# MCU-BLE.net
KiCad netlist of a schematic drawn in Altium Designer
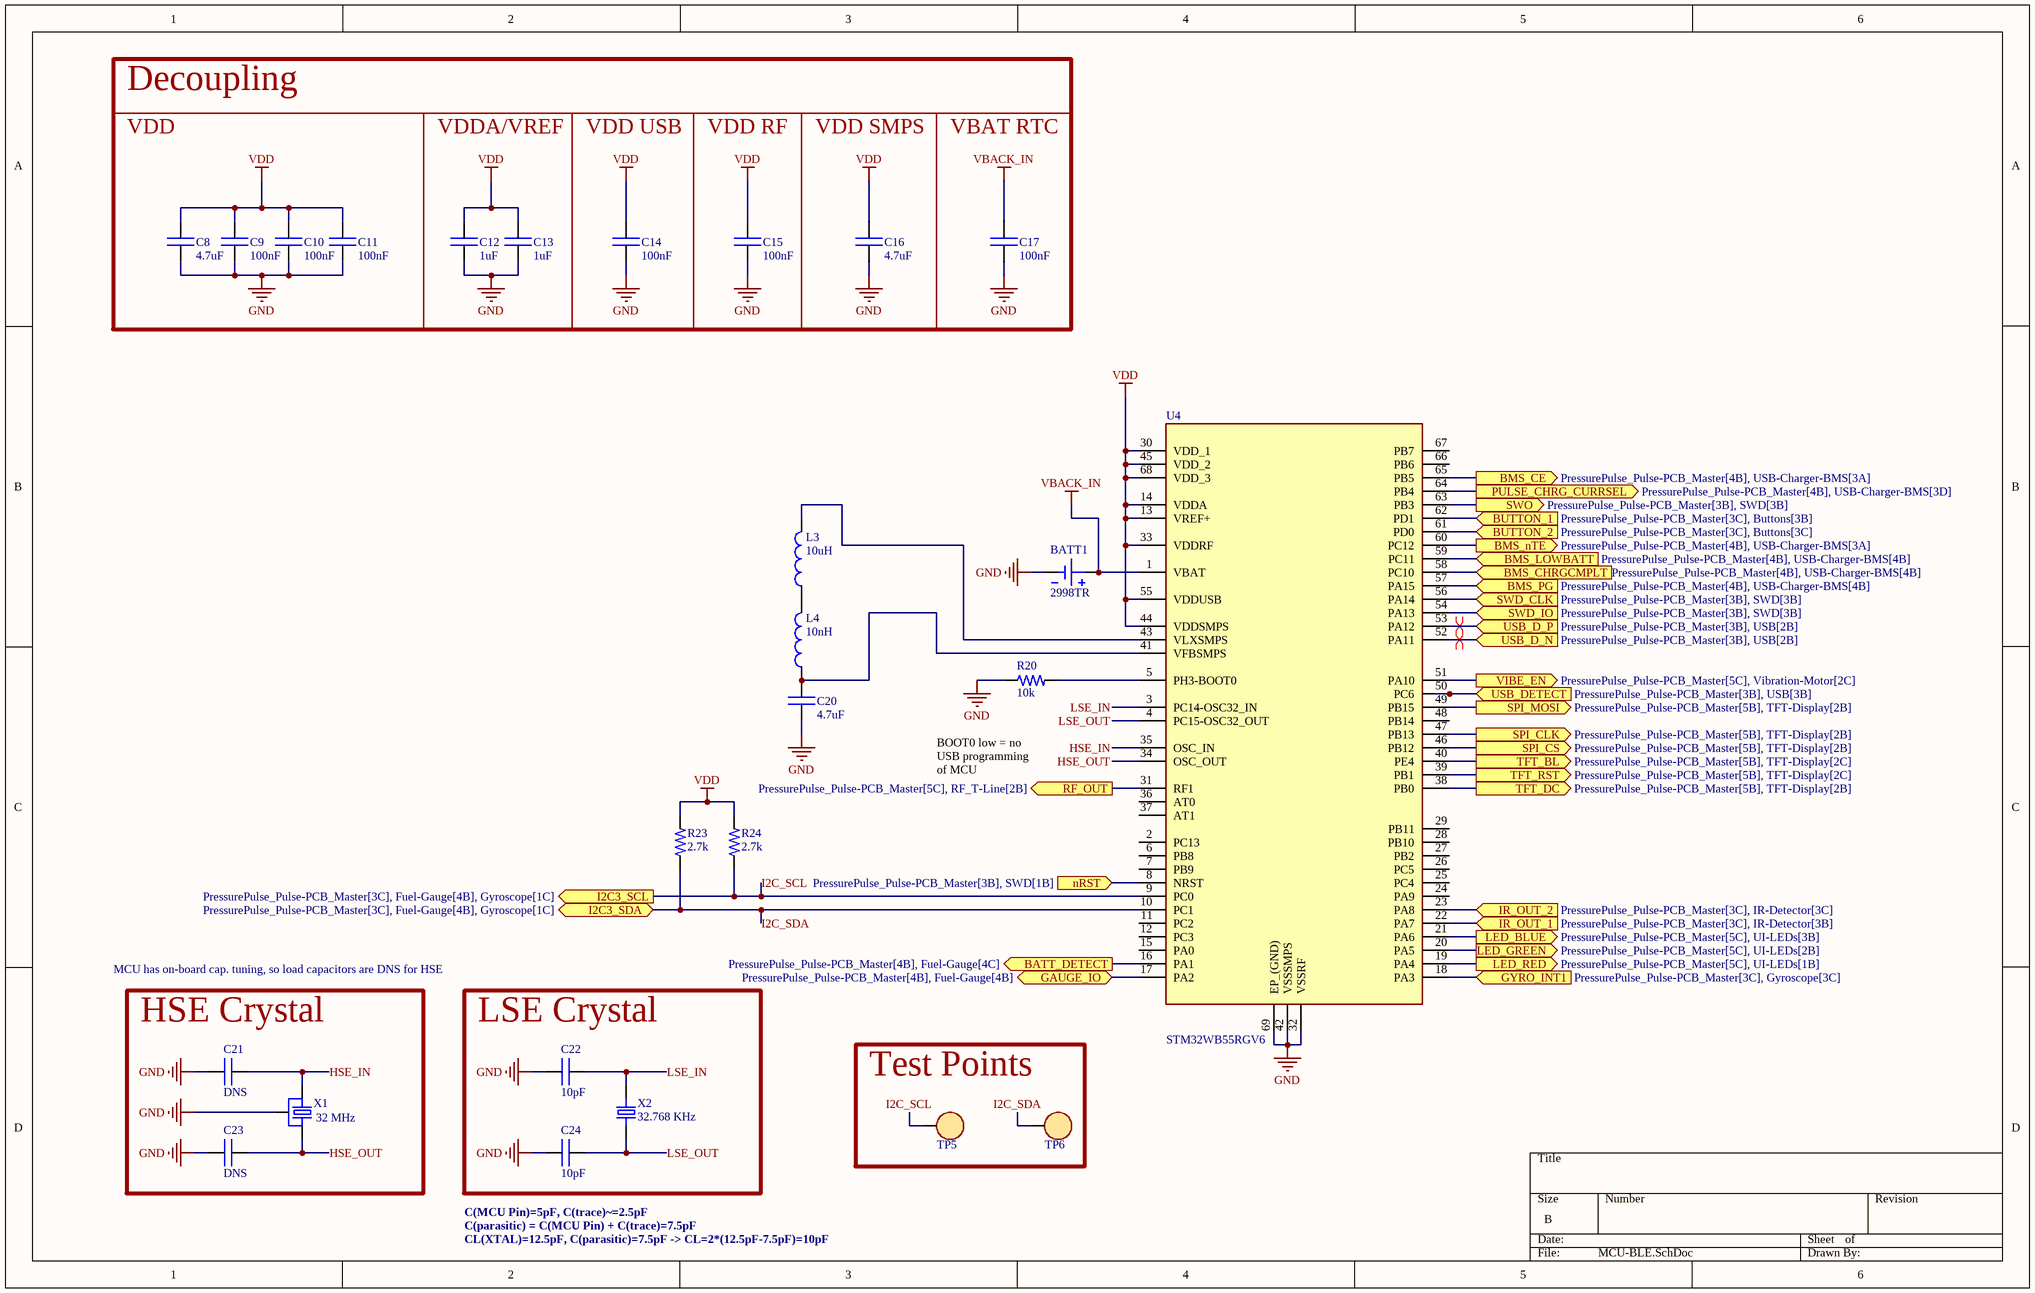
[diagram p0: MCU-BLE.SchDoc]

(export (version "E")
  (design (tool "Eeschema 10.0.6"))
  (components
    (comp (ref "BATT1")
      (value "2998TR")
      (footprint "PressurePulse:SR66")
      (description "Battery Holder (Open) Coin, 6.8mm, 1 Cell PC Pin")
      (fields (field (name "MFR") "Keystone Electronics"))
      (libsource (lib "PressurePulse") (part "COIN CELL BATT - SR66"))
    )
    (comp (ref "C8")
      (value "4.7uF")
      (footprint "PressurePulse:0402C")
      (description "Capaicitor")
      (fields (field (name "Comment") "CAP"))
      (libsource (lib "PressurePulse") (part "CAP"))
    )
    (comp (ref "C9")
      (value "100nF")
      (footprint "PressurePulse:0402C")
      (description "Capaicitor")
      (fields (field (name "Comment") "CAP"))
      (libsource (lib "PressurePulse") (part "CAP"))
    )
    (comp (ref "C10")
      (value "100nF")
      (footprint "PressurePulse:0402C")
      (description "Capaicitor")
      (fields (field (name "Comment") "CAP"))
      (libsource (lib "PressurePulse") (part "CAP"))
    )
    (comp (ref "C11")
      (value "100nF")
      (footprint "PressurePulse:0402C")
      (description "Capaicitor")
      (fields (field (name "Comment") "CAP"))
      (libsource (lib "PressurePulse") (part "CAP"))
    )
    (comp (ref "C12")
      (value "1uF")
      (footprint "PressurePulse:0402C")
      (description "Capaicitor")
      (fields (field (name "Comment") "CAP"))
      (libsource (lib "PressurePulse") (part "CAP"))
    )
    (comp (ref "C13")
      (value "1uF")
      (footprint "PressurePulse:0402C")
      (description "Capaicitor")
      (fields (field (name "Comment") "CAP"))
      (libsource (lib "PressurePulse") (part "CAP"))
    )
    (comp (ref "C14")
      (value "100nF")
      (footprint "PressurePulse:0402C")
      (description "Capaicitor")
      (fields (field (name "Comment") "CAP"))
      (libsource (lib "PressurePulse") (part "CAP"))
    )
    (comp (ref "C15")
      (value "100nF")
      (footprint "PressurePulse:0402C")
      (description "Capaicitor")
      (fields (field (name "Comment") "CAP"))
      (libsource (lib "PressurePulse") (part "CAP"))
    )
    (comp (ref "C16")
      (value "4.7uF")
      (footprint "PressurePulse:0402C")
      (description "Capaicitor")
      (fields (field (name "Comment") "CAP"))
      (libsource (lib "PressurePulse") (part "CAP"))
    )
    (comp (ref "C17")
      (value "100nF")
      (footprint "PressurePulse:0402C")
      (description "Capaicitor")
      (fields (field (name "Comment") "CAP"))
      (libsource (lib "PressurePulse") (part "CAP"))
    )
    (comp (ref "C20")
      (value "4.7uF")
      (footprint "PressurePulse:0402C")
      (description "Capaicitor")
      (fields (field (name "Comment") "CAP"))
      (libsource (lib "PressurePulse") (part "CAP"))
    )
    (comp (ref "C21")
      (value "DNS")
      (footprint "PressurePulse:0402C")
      (description "Capaicitor")
      (fields (field (name "Comment") "CAP"))
      (libsource (lib "PressurePulse") (part "CAP"))
    )
    (comp (ref "C22")
      (value "10pF")
      (footprint "PressurePulse:0402C")
      (description "Capaicitor")
      (fields (field (name "Comment") "CAP"))
      (libsource (lib "PressurePulse") (part "CAP"))
    )
    (comp (ref "C23")
      (value "DNS")
      (footprint "PressurePulse:0402C")
      (description "Capaicitor")
      (fields (field (name "Comment") "CAP"))
      (libsource (lib "PressurePulse") (part "CAP"))
    )
    (comp (ref "C24")
      (value "10pF")
      (footprint "PressurePulse:0402C")
      (description "Capaicitor")
      (fields (field (name "Comment") "CAP"))
      (libsource (lib "PressurePulse") (part "CAP"))
    )
    (comp (ref "L3")
      (value "10uH")
      (footprint "PressurePulse:0805L")
      (description "INDUCTOR")
      (fields (field (name "Comment") "IND"))
      (libsource (lib "PressurePulse") (part "IND"))
    )
    (comp (ref "L4")
      (value "10nH")
      (footprint "PressurePulse:0402L")
      (description "INDUCTOR")
      (fields (field (name "Comment") "IND"))
      (libsource (lib "PressurePulse") (part "IND"))
    )
    (comp (ref "R20")
      (value "10k")
      (footprint "PressurePulse:0402R")
      (description "Resistor")
      (fields (field (name "Comment") "RES"))
      (libsource (lib "PressurePulse") (part "RES"))
    )
    (comp (ref "R23")
      (value "2.7k")
      (footprint "PressurePulse:0402R")
      (description "Resistor")
      (fields (field (name "Comment") "RES"))
      (libsource (lib "PressurePulse") (part "RES"))
    )
    (comp (ref "R24")
      (value "2.7k")
      (footprint "PressurePulse:0402R")
      (description "Resistor")
      (fields (field (name "Comment") "RES"))
      (libsource (lib "PressurePulse") (part "RES"))
    )
    (comp (ref "TP5")
      (value "RH-5019")
      (footprint "PressurePulse:TP - RH-5019")
      (fields (field (name "MFR") "ronghe"))
      (libsource (lib "PressurePulse") (part "TEST POINT"))
    )
    (comp (ref "TP6")
      (value "RH-5019")
      (footprint "PressurePulse:TP - RH-5019")
      (fields (field (name "MFR") "ronghe"))
      (libsource (lib "PressurePulse") (part "TEST POINT"))
    )
    (comp (ref "U4")
      (value "STM32WB55RGV6")
      (footprint "PressurePulse:VQFN-68")
      (fields (field (name "MFR") "STMicroelectronics"))
      (libsource (lib "PressurePulse") (part "STM32WB55RGV6"))
    )
    (comp (ref "X1")
      (value "XTAL-OSC_32MHz")
      (footprint "PressurePulse:32MHZ_SMD1612-4P")
      (description "SMD Tuning Fork Crystal")
      (fields (field (name "FREQUENCY") "32 MHz"))
      (libsource (lib "PressurePulse") (part "XTAL-OSC_32MHz"))
    )
    (comp (ref "X2")
      (value "XTAL-OSC_32.768kHz")
      (footprint "PressurePulse:XTAL_ECS-.327-12.5-34B-TR")
      (description "32.768kHz 12.5pF ±20ppm SMD3215-2P  Crystals ROHS")
      (fields (field (name "MFR") "CITIZEN") (field (name "FREQUENCY") "32.768 KHz"))
      (libsource (lib "PressurePulse") (part "XTAL-OSC_32.768kHz"))
    )
  )
  (nets
    (net (code "1") (name "/BATT_DETECT") (class "Default")
      (node (ref "U4") (pin "16") (pinfunction "PA1_16") (pintype "passive"))
    )
    (net (code "2") (name "/BMS_CE") (class "Default")
      (node (ref "U4") (pin "65") (pinfunction "PB5_65") (pintype "passive"))
    )
    (net (code "3") (name "/BMS_CHRGCMPLT") (class "Default")
      (node (ref "U4") (pin "58") (pinfunction "PC10_58") (pintype "passive"))
    )
    (net (code "4") (name "/BMS_LOWBATT") (class "Default")
      (node (ref "U4") (pin "59") (pinfunction "PC11_59") (pintype "passive"))
    )
    (net (code "5") (name "/BMS_PG") (class "Default")
      (node (ref "U4") (pin "57") (pinfunction "PA15_57") (pintype "passive"))
    )
    (net (code "6") (name "/BMS_nTE") (class "Default")
      (node (ref "U4") (pin "60") (pinfunction "PC12_60") (pintype "passive"))
    )
    (net (code "7") (name "/BUTTON_1") (class "Default")
      (node (ref "U4") (pin "62") (pinfunction "PD1_62") (pintype "passive"))
    )
    (net (code "8") (name "/BUTTON_2") (class "Default")
      (node (ref "U4") (pin "61") (pinfunction "PD0_61") (pintype "passive"))
    )
    (net (code "9") (name "/GAUGE_IO") (class "Default")
      (node (ref "U4") (pin "17") (pinfunction "PA2_17") (pintype "passive"))
    )
    (net (code "10") (name "/GYRO_INT1") (class "Default")
      (node (ref "U4") (pin "18") (pinfunction "PA3_18") (pintype "passive"))
    )
    (net (code "11") (name "/HSE_IN") (class "Default")
      (node (ref "C21") (pin "1") (pinfunction "1_1") (pintype "passive"))
      (node (ref "U4") (pin "35") (pinfunction "OSC_IN_35") (pintype "passive"))
      (node (ref "X1") (pin "1") (pinfunction "1_1") (pintype "passive"))
    )
    (net (code "12") (name "/HSE_OUT") (class "Default")
      (node (ref "C23") (pin "1") (pinfunction "1_1") (pintype "passive"))
      (node (ref "U4") (pin "34") (pinfunction "OSC_OUT_34") (pintype "passive"))
      (node (ref "X1") (pin "3") (pinfunction "3_3") (pintype "passive"))
    )
    (net (code "13") (name "/I2C_SCL") (class "Default")
      (node (ref "R24") (pin "1") (pinfunction "1_1") (pintype "passive"))
      (node (ref "TP5") (pin "1") (pinfunction "1_1") (pintype "passive"))
      (node (ref "U4") (pin "9") (pinfunction "PC0_9") (pintype "passive"))
    )
    (net (code "14") (name "/I2C_SDA") (class "Default")
      (node (ref "R23") (pin "1") (pinfunction "1_1") (pintype "passive"))
      (node (ref "TP6") (pin "1") (pinfunction "1_1") (pintype "passive"))
      (node (ref "U4") (pin "10") (pinfunction "PC1_10") (pintype "passive"))
    )
    (net (code "15") (name "/IR_OUT_1") (class "Default")
      (node (ref "U4") (pin "22") (pinfunction "PA7_22") (pintype "passive"))
    )
    (net (code "16") (name "/IR_OUT_2") (class "Default")
      (node (ref "U4") (pin "23") (pinfunction "PA8_23") (pintype "passive"))
    )
    (net (code "17") (name "/LED_BLUE") (class "Default")
      (node (ref "U4") (pin "21") (pinfunction "PA6_21") (pintype "passive"))
    )
    (net (code "18") (name "/LED_GREEN") (class "Default")
      (node (ref "U4") (pin "20") (pinfunction "PA5_20") (pintype "passive"))
    )
    (net (code "19") (name "/LED_RED") (class "Default")
      (node (ref "U4") (pin "19") (pinfunction "PA4_19") (pintype "passive"))
    )
    (net (code "20") (name "/LSE_IN") (class "Default")
      (node (ref "C22") (pin "1") (pinfunction "1_1") (pintype "passive"))
      (node (ref "U4") (pin "3") (pinfunction "PC14-OSC32_IN_3") (pintype "passive"))
      (node (ref "X2") (pin "2") (pinfunction "2_2") (pintype "passive"))
    )
    (net (code "21") (name "/LSE_OUT") (class "Default")
      (node (ref "C24") (pin "1") (pinfunction "1_1") (pintype "passive"))
      (node (ref "U4") (pin "4") (pinfunction "PC15-OSC32_OUT_4") (pintype "passive"))
      (node (ref "X2") (pin "1") (pinfunction "1_1") (pintype "passive"))
    )
    (net (code "22") (name "/PULSE_CHRG_CURRSEL") (class "Default")
      (node (ref "U4") (pin "64") (pinfunction "PB4_64") (pintype "passive"))
    )
    (net (code "23") (name "/RF_OUT") (class "Default")
      (node (ref "U4") (pin "31") (pinfunction "RF1_31") (pintype "passive"))
    )
    (net (code "24") (name "/SPI_CLK") (class "Default")
      (node (ref "U4") (pin "47") (pinfunction "PB13_47") (pintype "passive"))
    )
    (net (code "25") (name "/SPI_CS") (class "Default")
      (node (ref "U4") (pin "46") (pinfunction "PB12_46") (pintype "passive"))
    )
    (net (code "26") (name "/SPI_MOSI") (class "Default")
      (node (ref "U4") (pin "49") (pinfunction "PB15_49") (pintype "passive"))
    )
    (net (code "27") (name "/SWD_CLK") (class "Default")
      (node (ref "U4") (pin "56") (pinfunction "PA14_56") (pintype "passive"))
    )
    (net (code "28") (name "/SWD_IO") (class "Default")
      (node (ref "U4") (pin "54") (pinfunction "PA13_54") (pintype "passive"))
    )
    (net (code "29") (name "/SWO") (class "Default")
      (node (ref "U4") (pin "63") (pinfunction "PB3_63") (pintype "passive"))
    )
    (net (code "30") (name "/TFT_BL") (class "Default")
      (node (ref "U4") (pin "40") (pinfunction "PE4_40") (pintype "passive"))
    )
    (net (code "31") (name "/TFT_DC") (class "Default")
      (node (ref "U4") (pin "38") (pinfunction "PB0_38") (pintype "passive"))
    )
    (net (code "32") (name "/TFT_RST") (class "Default")
      (node (ref "U4") (pin "39") (pinfunction "PB1_39") (pintype "passive"))
    )
    (net (code "33") (name "/USB_DETECT") (class "Default")
      (node (ref "U4") (pin "50") (pinfunction "PC6_50") (pintype "passive"))
    )
    (net (code "34") (name "/USB_D_N") (class "Default")
      (node (ref "U4") (pin "52") (pinfunction "PA11_52") (pintype "passive"))
    )
    (net (code "35") (name "/USB_D_P") (class "Default")
      (node (ref "U4") (pin "53") (pinfunction "PA12_53") (pintype "passive"))
    )
    (net (code "36") (name "/VIBE_EN") (class "Default")
      (node (ref "U4") (pin "51") (pinfunction "PA10_51") (pintype "passive"))
    )
    (net (code "37") (name "/nRST") (class "Default")
      (node (ref "U4") (pin "8") (pinfunction "NRST_8") (pintype "passive"))
    )
    (net (code "38") (name "GND") (class "Default")
      (node (ref "BATT1") (pin "N") (pinfunction "NEG_N") (pintype "passive"))
      (node (ref "C10") (pin "1") (pinfunction "1_1") (pintype "passive"))
      (node (ref "C11") (pin "1") (pinfunction "1_1") (pintype "passive"))
      (node (ref "C12") (pin "1") (pinfunction "1_1") (pintype "passive"))
      (node (ref "C13") (pin "1") (pinfunction "1_1") (pintype "passive"))
      (node (ref "C14") (pin "1") (pinfunction "1_1") (pintype "passive"))
      (node (ref "C15") (pin "1") (pinfunction "1_1") (pintype "passive"))
      (node (ref "C16") (pin "1") (pinfunction "1_1") (pintype "passive"))
      (node (ref "C17") (pin "1") (pinfunction "1_1") (pintype "passive"))
      (node (ref "C20") (pin "1") (pinfunction "1_1") (pintype "passive"))
      (node (ref "C21") (pin "2") (pinfunction "2_2") (pintype "passive"))
      (node (ref "C22") (pin "2") (pinfunction "2_2") (pintype "passive"))
      (node (ref "C23") (pin "2") (pinfunction "2_2") (pintype "passive"))
      (node (ref "C24") (pin "2") (pinfunction "2_2") (pintype "passive"))
      (node (ref "C8") (pin "1") (pinfunction "1_1") (pintype "passive"))
      (node (ref "C9") (pin "1") (pinfunction "1_1") (pintype "passive"))
      (node (ref "R20") (pin "1") (pinfunction "1_1") (pintype "passive"))
      (node (ref "U4") (pin "32") (pinfunction "VSSRF_32") (pintype "passive"))
      (node (ref "U4") (pin "42") (pinfunction "VSSSMPS_42") (pintype "passive"))
      (node (ref "U4") (pin "69") (pinfunction "EP_(GND)_69") (pintype "passive"))
      (node (ref "X1") (pin "GND") (pinfunction "GND_GND") (pintype "passive"))
    )
    (net (code "39") (name "Net-(L3-Pad1)") (class "Default")
      (node (ref "L3") (pin "1") (pinfunction "1_1") (pintype "passive"))
      (node (ref "L4") (pin "2") (pinfunction "2_2") (pintype "passive"))
    )
    (net (code "40") (name "Net-(U4-PH3-BOOT0)") (class "Default")
      (node (ref "R20") (pin "2") (pinfunction "2_2") (pintype "passive"))
      (node (ref "U4") (pin "5") (pinfunction "PH3-BOOT0_5") (pintype "passive"))
    )
    (net (code "41") (name "Net-(U4-VFBSMPS)") (class "Default")
      (node (ref "C20") (pin "2") (pinfunction "2_2") (pintype "passive"))
      (node (ref "L4") (pin "1") (pinfunction "1_1") (pintype "passive"))
      (node (ref "U4") (pin "41") (pinfunction "VFBSMPS_41") (pintype "passive"))
    )
    (net (code "42") (name "Net-(U4-VLXSMPS)") (class "Default")
      (node (ref "L3") (pin "2") (pinfunction "2_2") (pintype "passive"))
      (node (ref "U4") (pin "43") (pinfunction "VLXSMPS_43") (pintype "passive"))
    )
    (net (code "43") (name "VBACK_IN") (class "Default")
      (node (ref "BATT1") (pin "P") (pinfunction "POS_P") (pintype "passive"))
      (node (ref "C17") (pin "2") (pinfunction "2_2") (pintype "passive"))
      (node (ref "U4") (pin "1") (pinfunction "VBAT_1") (pintype "passive"))
    )
    (net (code "44") (name "VDD") (class "Default")
      (node (ref "C10") (pin "2") (pinfunction "2_2") (pintype "passive"))
      (node (ref "C11") (pin "2") (pinfunction "2_2") (pintype "passive"))
      (node (ref "C12") (pin "2") (pinfunction "2_2") (pintype "passive"))
      (node (ref "C13") (pin "2") (pinfunction "2_2") (pintype "passive"))
      (node (ref "C14") (pin "2") (pinfunction "2_2") (pintype "passive"))
      (node (ref "C15") (pin "2") (pinfunction "2_2") (pintype "passive"))
      (node (ref "C16") (pin "2") (pinfunction "2_2") (pintype "passive"))
      (node (ref "C8") (pin "2") (pinfunction "2_2") (pintype "passive"))
      (node (ref "C9") (pin "2") (pinfunction "2_2") (pintype "passive"))
      (node (ref "R23") (pin "2") (pinfunction "2_2") (pintype "passive"))
      (node (ref "R24") (pin "2") (pinfunction "2_2") (pintype "passive"))
      (node (ref "U4") (pin "13") (pinfunction "VREF+_13") (pintype "passive"))
      (node (ref "U4") (pin "14") (pinfunction "VDDA_14") (pintype "passive"))
      (node (ref "U4") (pin "30") (pinfunction "VDD_1_30") (pintype "passive"))
      (node (ref "U4") (pin "33") (pinfunction "VDDRF_33") (pintype "passive"))
      (node (ref "U4") (pin "44") (pinfunction "VDDSMPS_44") (pintype "passive"))
      (node (ref "U4") (pin "45") (pinfunction "VDD_2_45") (pintype "passive"))
      (node (ref "U4") (pin "55") (pinfunction "VDDUSB_55") (pintype "passive"))
      (node (ref "U4") (pin "68") (pinfunction "VDD_3_68") (pintype "passive"))
    )
    (net (code "45") (name "unconnected-(U4-AT0-Pad36)") (class "Default")
      (node (ref "U4") (pin "36") (pinfunction "AT0_36") (pintype "passive"))
    )
    (net (code "46") (name "unconnected-(U4-AT1-Pad37)") (class "Default")
      (node (ref "U4") (pin "37") (pinfunction "AT1_37") (pintype "passive"))
    )
    (net (code "47") (name "unconnected-(U4-PA0-Pad15)") (class "Default")
      (node (ref "U4") (pin "15") (pinfunction "PA0_15") (pintype "passive"))
    )
    (net (code "48") (name "unconnected-(U4-PA9-Pad24)") (class "Default")
      (node (ref "U4") (pin "24") (pinfunction "PA9_24") (pintype "passive"))
    )
    (net (code "49") (name "unconnected-(U4-PB2-Pad27)") (class "Default")
      (node (ref "U4") (pin "27") (pinfunction "PB2_27") (pintype "passive"))
    )
    (net (code "50") (name "unconnected-(U4-PB6-Pad66)") (class "Default")
      (node (ref "U4") (pin "66") (pinfunction "PB6_66") (pintype "passive"))
    )
    (net (code "51") (name "unconnected-(U4-PB7-Pad67)") (class "Default")
      (node (ref "U4") (pin "67") (pinfunction "PB7_67") (pintype "passive"))
    )
    (net (code "52") (name "unconnected-(U4-PB8-Pad6)") (class "Default")
      (node (ref "U4") (pin "6") (pinfunction "PB8_6") (pintype "passive"))
    )
    (net (code "53") (name "unconnected-(U4-PB9-Pad7)") (class "Default")
      (node (ref "U4") (pin "7") (pinfunction "PB9_7") (pintype "passive"))
    )
    (net (code "54") (name "unconnected-(U4-PB10-Pad28)") (class "Default")
      (node (ref "U4") (pin "28") (pinfunction "PB10_28") (pintype "passive"))
    )
    (net (code "55") (name "unconnected-(U4-PB11-Pad29)") (class "Default")
      (node (ref "U4") (pin "29") (pinfunction "PB11_29") (pintype "passive"))
    )
    (net (code "56") (name "unconnected-(U4-PB14-Pad48)") (class "Default")
      (node (ref "U4") (pin "48") (pinfunction "PB14_48") (pintype "passive"))
    )
    (net (code "57") (name "unconnected-(U4-PC2-Pad11)") (class "Default")
      (node (ref "U4") (pin "11") (pinfunction "PC2_11") (pintype "passive"))
    )
    (net (code "58") (name "unconnected-(U4-PC3-Pad12)") (class "Default")
      (node (ref "U4") (pin "12") (pinfunction "PC3_12") (pintype "passive"))
    )
    (net (code "59") (name "unconnected-(U4-PC4-Pad25)") (class "Default")
      (node (ref "U4") (pin "25") (pinfunction "PC4_25") (pintype "passive"))
    )
    (net (code "60") (name "unconnected-(U4-PC5-Pad26)") (class "Default")
      (node (ref "U4") (pin "26") (pinfunction "PC5_26") (pintype "passive"))
    )
    (net (code "61") (name "unconnected-(U4-PC13-Pad2)") (class "Default")
      (node (ref "U4") (pin "2") (pinfunction "PC13_2") (pintype "passive"))
    )
  )
)
